# Gateway_v1_0.net
KiCad netlist of a schematic drawn in EAGLE
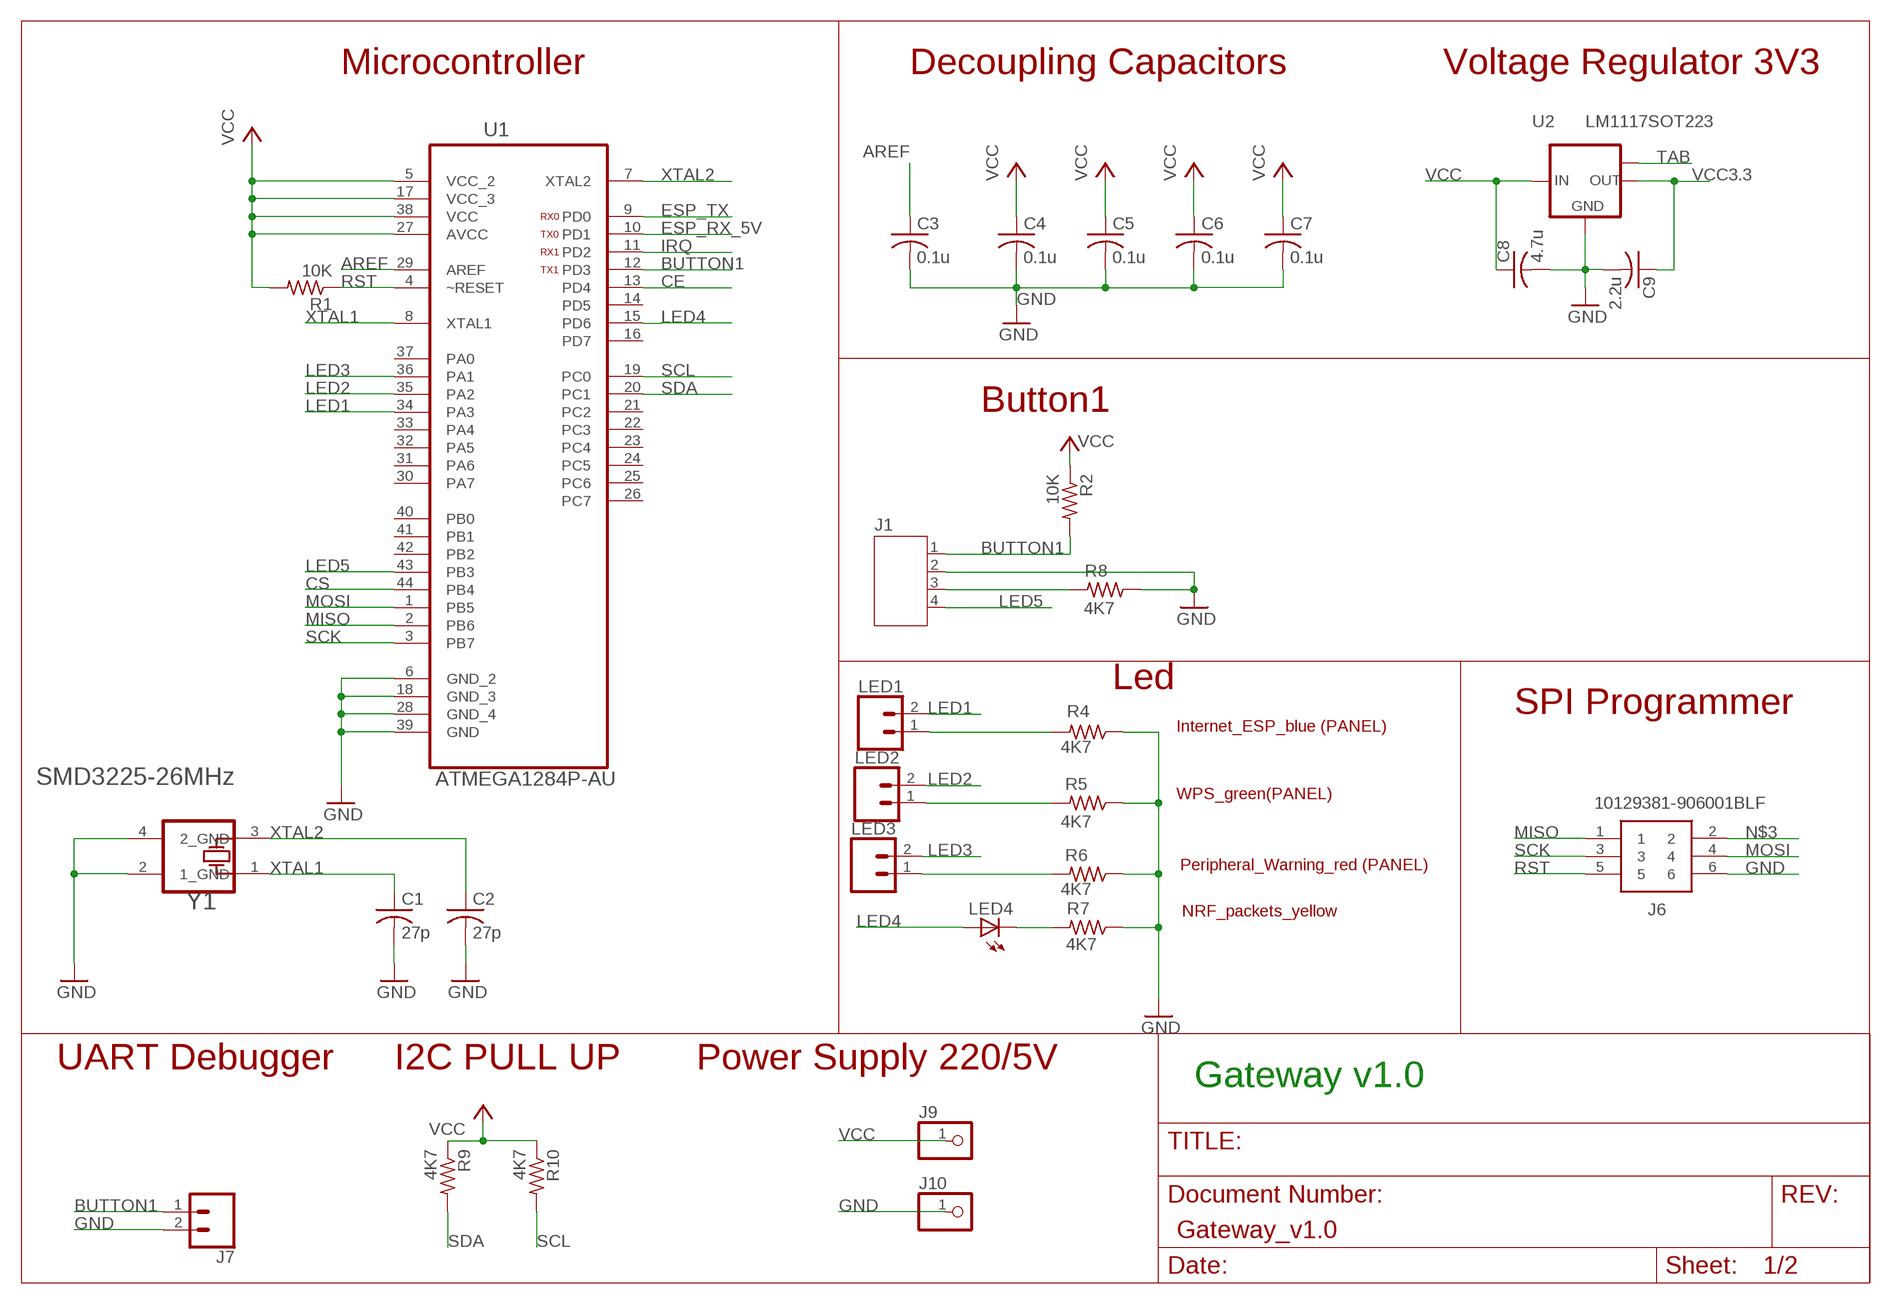
[diagram p0: schematic, sheet 1]
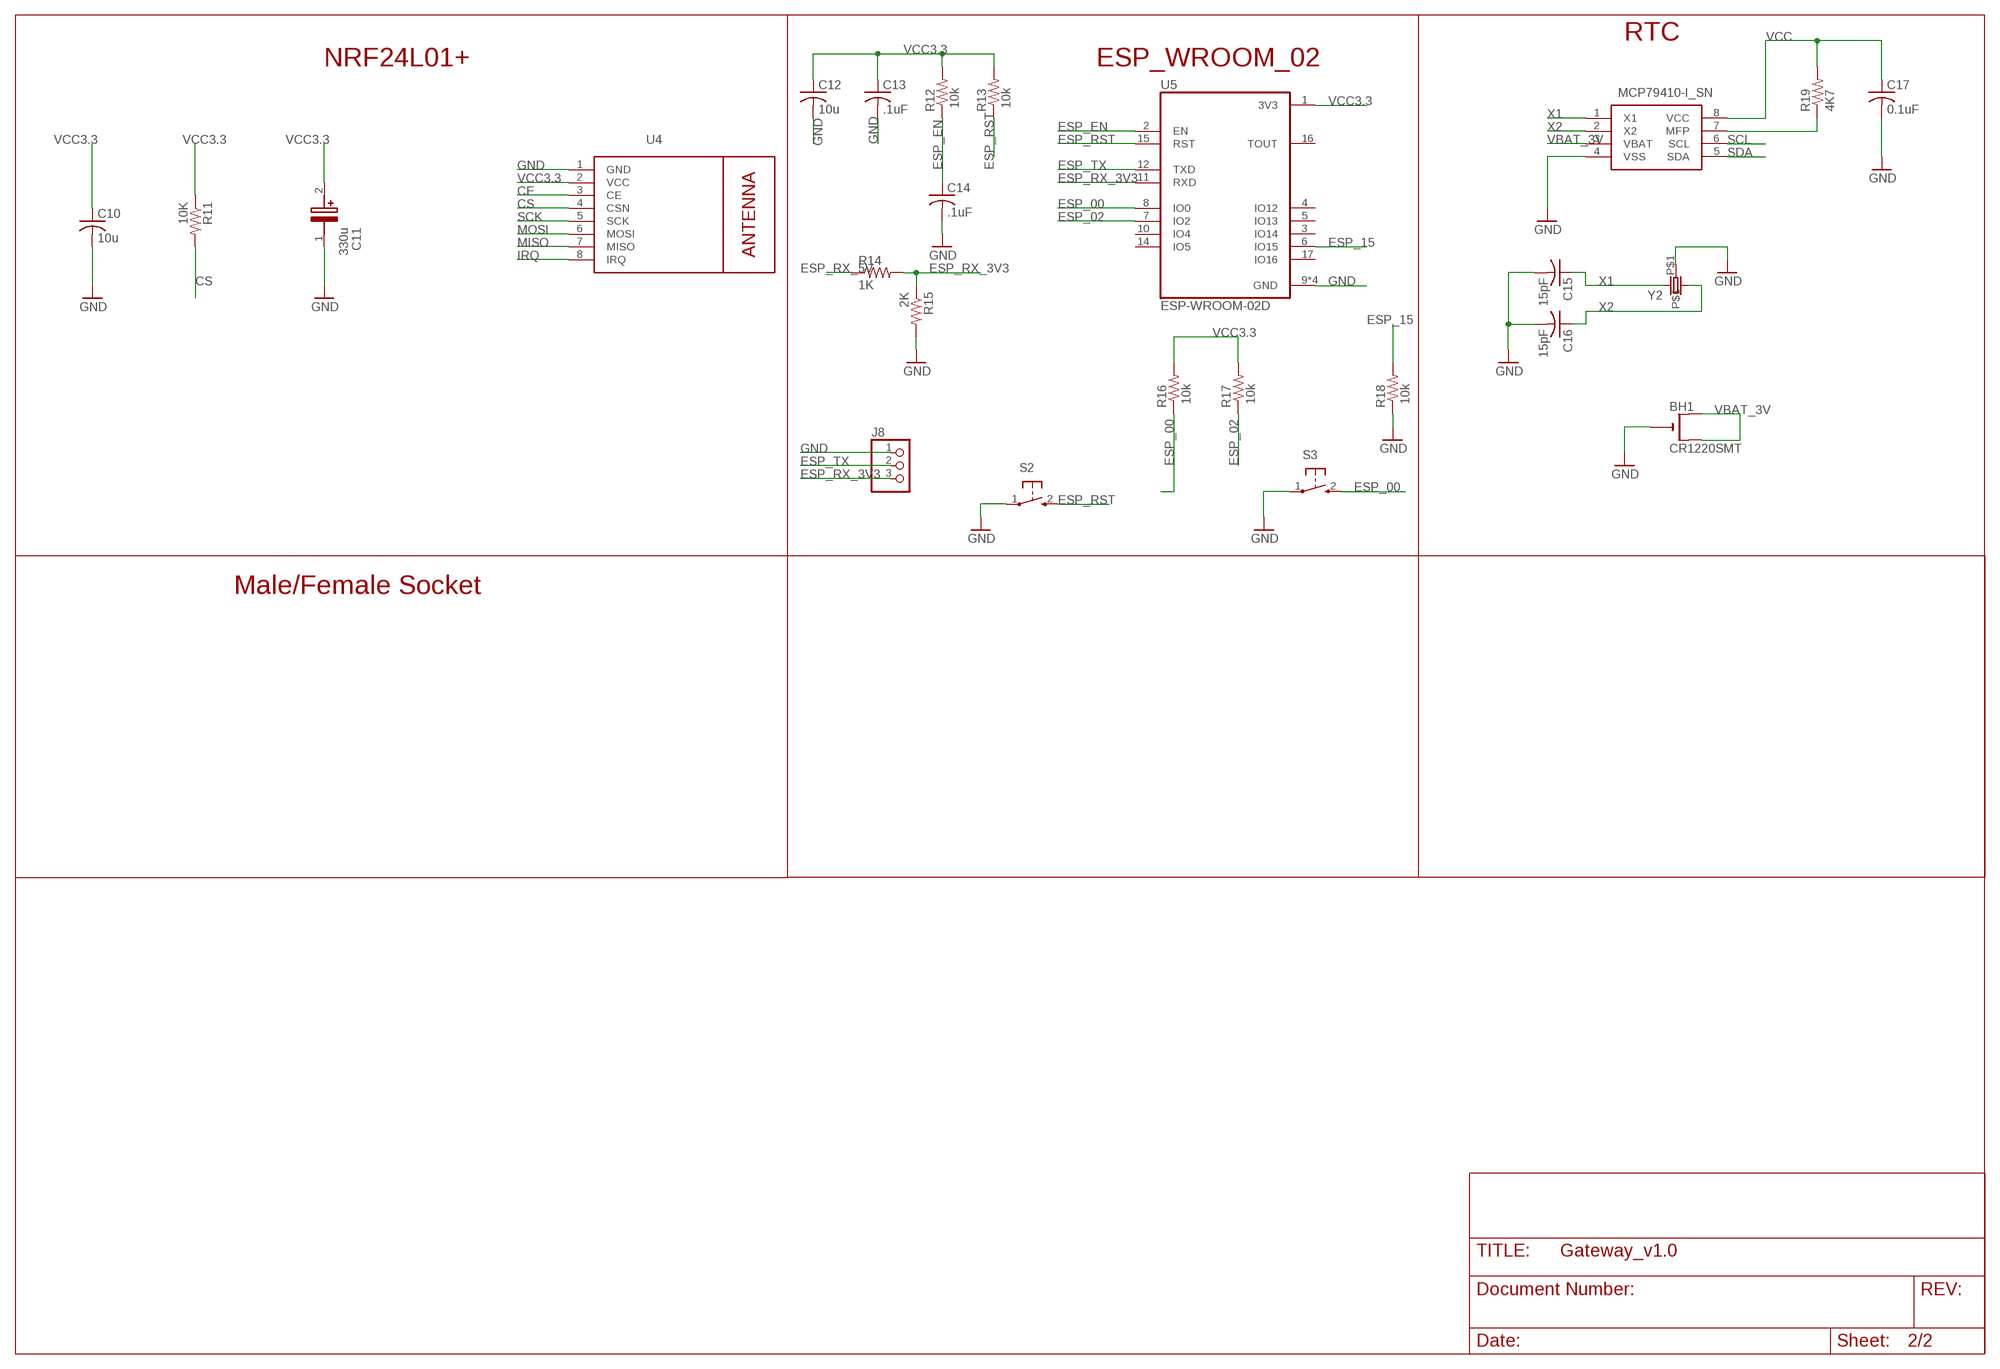
[diagram p1: schematic, sheet 2]

(export (version "E")
  (design (tool "Eeschema 10.0.6"))
  (components
    (comp (ref "C1")
      (value "27p")
      (footprint "eagle-import:SMD-0805")
      (libsource (lib "eagle-import") (part "CAPACITOR-SMD-0805"))
    )
    (comp (ref "C2")
      (value "27p")
      (footprint "eagle-import:SMD-0805")
      (libsource (lib "eagle-import") (part "CAPACITOR-SMD-0805"))
    )
    (comp (ref "C3")
      (value "0.1u")
      (footprint "eagle-import:SMD-0805")
      (libsource (lib "eagle-import") (part "CAPACITOR-SMD-0805"))
    )
    (comp (ref "C4")
      (value "0.1u")
      (footprint "eagle-import:SMD-0805")
      (libsource (lib "eagle-import") (part "CAPACITOR-SMD-0805"))
    )
    (comp (ref "C5")
      (value "0.1u")
      (footprint "eagle-import:SMD-0805")
      (libsource (lib "eagle-import") (part "CAPACITOR-SMD-0805"))
    )
    (comp (ref "C6")
      (value "0.1u")
      (footprint "eagle-import:SMD-0805")
      (libsource (lib "eagle-import") (part "CAPACITOR-SMD-0805"))
    )
    (comp (ref "C7")
      (value "0.1u")
      (footprint "eagle-import:SMD-0805")
      (libsource (lib "eagle-import") (part "CAPACITOR-SMD-0805"))
    )
    (comp (ref "C8")
      (value "4.7u")
      (footprint "eagle-import:SMD-0805")
      (libsource (lib "eagle-import") (part "CAPACITOR-SMD-0805"))
    )
    (comp (ref "C9")
      (value "2.2u")
      (footprint "eagle-import:SMD-0805")
      (libsource (lib "eagle-import") (part "CAPACITOR-SMD-0805"))
    )
    (comp (ref "J1")
      (value "JST-PH4")
      (footprint "eagle-import:JST-PH4")
      (libsource (lib "eagle-import") (part "JST-PH4"))
    )
    (comp (ref "J6")
      (value "10129381-906001BLF")
      (footprint "eagle-import:HDRV6W67P254_2X3_762X483X858P")
      (fields (field (name "MOUSER_PART_NUMBER") "649-1012938190601BLF"))
      (libsource (lib "eagle-import") (part "10129381-906001BLF"))
    )
    (comp (ref "J7")
      (value "CONN_02")
      (footprint "eagle-import:1X02")
      (libsource (lib "eagle-import") (part "CONN_02"))
    )
    (comp (ref "J9")
      (value "PINHD-1X1CB")
      (footprint "eagle-import:1X01-CLEANBIG")
      (libsource (lib "eagle-import") (part "PINHD-1X1CB"))
    )
    (comp (ref "J10")
      (value "PINHD-1X1CB")
      (footprint "eagle-import:1X01-CLEANBIG")
      (libsource (lib "eagle-import") (part "PINHD-1X1CB"))
    )
    (comp (ref "LED1")
      (value "CONN_02")
      (footprint "eagle-import:1X02")
      (libsource (lib "eagle-import") (part "CONN_02"))
    )
    (comp (ref "LED2")
      (value "CONN_02")
      (footprint "eagle-import:1X02")
      (libsource (lib "eagle-import") (part "CONN_02"))
    )
    (comp (ref "LED3")
      (value "CONN_02")
      (footprint "eagle-import:1X02")
      (libsource (lib "eagle-import") (part "CONN_02"))
    )
    (comp (ref "LED4")
      (value "LED4")
      (footprint "eagle-import:SMD-0805-LED")
      (libsource (lib "eagle-import") (part "LED-SMD-0805"))
    )
    (comp (ref "R1")
      (value "10K")
      (footprint "eagle-import:SMD-0805")
      (libsource (lib "eagle-import") (part "RESISTOR-SMD-0805"))
    )
    (comp (ref "R2")
      (value "10K")
      (footprint "eagle-import:SMD-0805")
      (libsource (lib "eagle-import") (part "RESISTOR-SMD-0805"))
    )
    (comp (ref "R4")
      (value "4K7")
      (footprint "eagle-import:SMD-0805")
      (libsource (lib "eagle-import") (part "RESISTOR-SMD-0805"))
    )
    (comp (ref "R5")
      (value "4K7")
      (footprint "eagle-import:SMD-0805")
      (libsource (lib "eagle-import") (part "RESISTOR-SMD-0805"))
    )
    (comp (ref "R6")
      (value "4K7")
      (footprint "eagle-import:SMD-0805")
      (libsource (lib "eagle-import") (part "RESISTOR-SMD-0805"))
    )
    (comp (ref "R7")
      (value "4K7")
      (footprint "eagle-import:SMD-0805")
      (libsource (lib "eagle-import") (part "RESISTOR-SMD-0805"))
    )
    (comp (ref "R8")
      (value "4K7")
      (footprint "eagle-import:SMD-0805")
      (libsource (lib "eagle-import") (part "RESISTOR-SMD-0805"))
    )
    (comp (ref "R9")
      (value "4K7")
      (footprint "eagle-import:SMD-0805")
      (libsource (lib "eagle-import") (part "RESISTOR-SMD-0805"))
    )
    (comp (ref "R10")
      (value "4K7")
      (footprint "eagle-import:SMD-0805")
      (libsource (lib "eagle-import") (part "RESISTOR-SMD-0805"))
    )
    (comp (ref "U1")
      (value "ATMEGA1284P-AU")
      (footprint "eagle-import:QFP80P1200X1200X120-44N")
      (fields (field (name "MF") "Microchip"))
      (libsource (lib "eagle-import") (part "ATMEGA1284P-AU"))
    )
    (comp (ref "U2")
      (value "LM1117SOT223")
      (footprint "eagle-import:SOT223")
      (libsource (lib "eagle-import") (part "LM1117MPX-3.3"))
    )
    (comp (ref "Y1")
      (value "TND_ELECTRONIC_SMD3225-26MHZTND_ELECTRONIC_SMD3225-26MHZ_0_0")
      (footprint "eagle-import:TND_ELECTRONIC_SMD3225-26MHZ_0")
      (fields (field (name "MF") "TND Electronic") (field (name "MPN") "SMD3225-26MHz"))
      (libsource (lib "eagle-import") (part "TND_ELECTRONIC_SMD3225-26MHZTND_ELECTRONIC_SMD3225-26MHZ_0_0"))
    )
    (comp (ref "BH1")
      (value "CR1220SMT")
      (footprint "eagle-import:CR1220-SMD")
      (fields (field (name "MF") "FDK America,") (field (name "MP") "CR1220"))
      (libsource (lib "eagle-import") (part "CR1220SMT"))
    )
    (comp (ref "C10")
      (value "10u")
      (footprint "eagle-import:SMD-0805")
      (libsource (lib "eagle-import") (part "CAPACITOR-SMD-0805"))
    )
    (comp (ref "C11")
      (value "330u")
      (footprint "eagle-import:SMD_LYTIC_D8")
      (fields
        (field (name "MANUFACTURER_PART_NUMBER") "EEE-FNC271XUP")
        (field (name "MOUSER_PART_NUMBER") "667-EEE-FNC271XUP")
      )
      (libsource (lib "eagle-import") (part "EEE-FNC271XUP"))
    )
    (comp (ref "C12")
      (value "10u")
      (footprint "eagle-import:SMD-0805")
      (libsource (lib "eagle-import") (part "CAPACITOR-SMD-0805"))
    )
    (comp (ref "C13")
      (value ".1uF")
      (footprint "eagle-import:SMD-0805")
      (libsource (lib "eagle-import") (part "CAPACITOR-SMD-0805"))
    )
    (comp (ref "C14")
      (value ".1uF")
      (footprint "eagle-import:SMD-0805")
      (libsource (lib "eagle-import") (part "CAPACITOR-SMD-0805"))
    )
    (comp (ref "C15")
      (value "15pF")
      (footprint "eagle-import:SMD-0805")
      (libsource (lib "eagle-import") (part "CAPACITOR-SMD-0805"))
    )
    (comp (ref "C16")
      (value "15pF")
      (footprint "eagle-import:SMD-0805")
      (libsource (lib "eagle-import") (part "CAPACITOR-SMD-0805"))
    )
    (comp (ref "C17")
      (value "0.1uF")
      (footprint "eagle-import:SMD-0805")
      (libsource (lib "eagle-import") (part "CAPACITOR-SMD-0805"))
    )
    (comp (ref "J8")
      (value "PINHD-1X3")
      (footprint "eagle-import:1X03")
      (libsource (lib "eagle-import") (part "PINHD-1X3"))
    )
    (comp (ref "R11")
      (value "10K")
      (footprint "eagle-import:SMD-0805")
      (libsource (lib "eagle-import") (part "RESISTOR-SMD-0805"))
    )
    (comp (ref "R12")
      (value "10k")
      (footprint "eagle-import:SMD-0805")
      (libsource (lib "eagle-import") (part "RESISTOR-SMD-0805"))
    )
    (comp (ref "R13")
      (value "10k")
      (footprint "eagle-import:SMD-0805")
      (libsource (lib "eagle-import") (part "RESISTOR-SMD-0805"))
    )
    (comp (ref "R14")
      (value "1K")
      (footprint "eagle-import:SMD-0805")
      (libsource (lib "eagle-import") (part "RESISTOR-SMD-0805"))
    )
    (comp (ref "R15")
      (value "2K")
      (footprint "eagle-import:SMD-0805")
      (libsource (lib "eagle-import") (part "RESISTOR-SMD-0805"))
    )
    (comp (ref "R16")
      (value "10k")
      (footprint "eagle-import:SMD-0805")
      (libsource (lib "eagle-import") (part "RESISTOR-SMD-0805"))
    )
    (comp (ref "R17")
      (value "10k")
      (footprint "eagle-import:SMD-0805")
      (libsource (lib "eagle-import") (part "RESISTOR-SMD-0805"))
    )
    (comp (ref "R18")
      (value "10k")
      (footprint "eagle-import:SMD-0805")
      (libsource (lib "eagle-import") (part "RESISTOR-SMD-0805"))
    )
    (comp (ref "R19")
      (value "4K7")
      (footprint "eagle-import:SMD-0805")
      (libsource (lib "eagle-import") (part "RESISTOR-SMD-0805"))
    )
    (comp (ref "S2")
      (value "SPST_TACT-KMR2")
      (footprint "eagle-import:KMR2")
      (libsource (lib "eagle-import") (part "SPST_TACT-KMR2"))
    )
    (comp (ref "S3")
      (value "SPST_TACT-KMR2")
      (footprint "eagle-import:KMR2")
      (libsource (lib "eagle-import") (part "SPST_TACT-KMR2"))
    )
    (comp (ref "U4")
      (value "WIRELESS-NRF24L01")
      (footprint "eagle-import:WIRELESS-NRF24L01")
      (libsource (lib "eagle-import") (part "WIRELESS-NRF24L01"))
    )
    (comp (ref "U5")
      (value "ESP-WROOM-02D")
      (footprint "eagle-import:MODULE_ESP-WROOM-02D")
      (fields (field (name "MF") "Espressif Systems"))
      (libsource (lib "eagle-import") (part "ESP-WROOM-02D"))
    )
    (comp (ref "U6")
      (value "MCP79410-I_SN")
      (footprint "eagle-import:SOIC127P600X175-8N")
      (fields
        (field (name "MANUFACTURER_PART_NUMBER") "MCP79410-I/SN")
        (field (name "MOUSER_PART_NUMBER") "579-MCP79410-I/SN")
      )
      (libsource (lib "eagle-import") (part "MCP79410-I_SN"))
    )
    (comp (ref "Y2")
      (value "CRYSTALTC26H")
      (footprint "eagle-import:TC26H")
      (libsource (lib "eagle-import") (part "CRYSTALTC26H"))
    )
  )
  (nets
    (net (code "1") (name "AREF") (class "Default")
      (node (ref "C3") (pin "1") (pinfunction "1_1") (pintype "passive"))
      (node (ref "U1") (pin "29") (pinfunction "AREF_29") (pintype "input"))
    )
    (net (code "2") (name "BUTTON1") (class "Default")
      (node (ref "J1") (pin "1") (pinfunction "1_1") (pintype "passive"))
      (node (ref "J7") (pin "1") (pinfunction "1_1") (pintype "passive"))
      (node (ref "R2") (pin "2") (pinfunction "2_2") (pintype "passive"))
      (node (ref "U1") (pin "12") (pinfunction "PD3_12") (pintype "bidirectional"))
    )
    (net (code "3") (name "CE") (class "Default")
      (node (ref "U1") (pin "13") (pinfunction "PD4_13") (pintype "bidirectional"))
      (node (ref "U4") (pin "3") (pinfunction "CE_3") (pintype "bidirectional"))
    )
    (net (code "4") (name "CS") (class "Default")
      (node (ref "R11") (pin "2") (pinfunction "2_2") (pintype "passive"))
      (node (ref "U1") (pin "44") (pinfunction "PB4_44") (pintype "bidirectional"))
      (node (ref "U4") (pin "4") (pinfunction "CSN_4") (pintype "bidirectional"))
    )
    (net (code "5") (name "ESP_00") (class "Default")
      (node (ref "R16") (pin "1") (pinfunction "1_1") (pintype "passive"))
      (node (ref "S3") (pin "2") (pinfunction "S_2") (pintype "passive"))
      (node (ref "U5") (pin "8") (pinfunction "IO0_8") (pintype "bidirectional"))
    )
    (net (code "6") (name "ESP_02") (class "Default")
      (node (ref "R17") (pin "1") (pinfunction "1_1") (pintype "passive"))
      (node (ref "U5") (pin "7") (pinfunction "IO2_7") (pintype "bidirectional"))
    )
    (net (code "7") (name "ESP_15") (class "Default")
      (node (ref "R18") (pin "2") (pinfunction "2_2") (pintype "passive"))
      (node (ref "U5") (pin "6") (pinfunction "IO15_6") (pintype "bidirectional"))
    )
    (net (code "8") (name "ESP_EN") (class "Default")
      (node (ref "C14") (pin "1") (pinfunction "1_1") (pintype "passive"))
      (node (ref "R12") (pin "1") (pinfunction "1_1") (pintype "passive"))
      (node (ref "U5") (pin "2") (pinfunction "EN_2") (pintype "input"))
    )
    (net (code "9") (name "ESP_RST") (class "Default")
      (node (ref "R13") (pin "1") (pinfunction "1_1") (pintype "passive"))
      (node (ref "S2") (pin "2") (pinfunction "S_2") (pintype "passive"))
      (node (ref "U5") (pin "15") (pinfunction "RST_15") (pintype "input"))
    )
    (net (code "10") (name "ESP_RX_3V3") (class "Default")
      (node (ref "J8") (pin "3") (pinfunction "3_3") (pintype "passive"))
      (node (ref "R14") (pin "2") (pinfunction "2_2") (pintype "passive"))
      (node (ref "R15") (pin "1") (pinfunction "1_1") (pintype "passive"))
      (node (ref "U5") (pin "11") (pinfunction "RXD_11") (pintype "bidirectional"))
    )
    (net (code "11") (name "ESP_RX_5V") (class "Default")
      (node (ref "R14") (pin "1") (pinfunction "1_1") (pintype "passive"))
      (node (ref "U1") (pin "10") (pinfunction "PD1_10") (pintype "bidirectional"))
    )
    (net (code "12") (name "ESP_TX") (class "Default")
      (node (ref "J8") (pin "2") (pinfunction "2_2") (pintype "passive"))
      (node (ref "U1") (pin "9") (pinfunction "PD0_9") (pintype "bidirectional"))
      (node (ref "U5") (pin "12") (pinfunction "TXD_12") (pintype "bidirectional"))
    )
    (net (code "13") (name "GND") (class "Default")
      (node (ref "BH1") (pin "-") (pinfunction "-_-") (pintype "passive"))
      (node (ref "C1") (pin "2") (pinfunction "2_2") (pintype "passive"))
      (node (ref "C10") (pin "2") (pinfunction "2_2") (pintype "passive"))
      (node (ref "C11") (pin "1") (pinfunction "1_1") (pintype "bidirectional"))
      (node (ref "C12") (pin "2") (pinfunction "2_2") (pintype "passive"))
      (node (ref "C13") (pin "2") (pinfunction "2_2") (pintype "passive"))
      (node (ref "C14") (pin "2") (pinfunction "2_2") (pintype "passive"))
      (node (ref "C15") (pin "2") (pinfunction "2_2") (pintype "passive"))
      (node (ref "C16") (pin "2") (pinfunction "2_2") (pintype "passive"))
      (node (ref "C17") (pin "2") (pinfunction "2_2") (pintype "passive"))
      (node (ref "C2") (pin "2") (pinfunction "2_2") (pintype "passive"))
      (node (ref "C3") (pin "2") (pinfunction "2_2") (pintype "passive"))
      (node (ref "C4") (pin "2") (pinfunction "2_2") (pintype "passive"))
      (node (ref "C5") (pin "2") (pinfunction "2_2") (pintype "passive"))
      (node (ref "C6") (pin "2") (pinfunction "2_2") (pintype "passive"))
      (node (ref "C7") (pin "2") (pinfunction "2_2") (pintype "passive"))
      (node (ref "C8") (pin "2") (pinfunction "2_2") (pintype "passive"))
      (node (ref "C9") (pin "2") (pinfunction "2_2") (pintype "passive"))
      (node (ref "J1") (pin "2") (pinfunction "2_2") (pintype "passive"))
      (node (ref "J10") (pin "1") (pinfunction "1_1") (pintype "passive"))
      (node (ref "J6") (pin "6") (pinfunction "6_6") (pintype "bidirectional"))
      (node (ref "J7") (pin "2") (pinfunction "2_2") (pintype "passive"))
      (node (ref "J8") (pin "1") (pinfunction "1_1") (pintype "passive"))
      (node (ref "R15") (pin "2") (pinfunction "2_2") (pintype "passive"))
      (node (ref "R18") (pin "1") (pinfunction "1_1") (pintype "passive"))
      (node (ref "R4") (pin "1") (pinfunction "1_1") (pintype "passive"))
      (node (ref "R5") (pin "1") (pinfunction "1_1") (pintype "passive"))
      (node (ref "R6") (pin "1") (pinfunction "1_1") (pintype "passive"))
      (node (ref "R7") (pin "1") (pinfunction "1_1") (pintype "passive"))
      (node (ref "R8") (pin "1") (pinfunction "1_1") (pintype "passive"))
      (node (ref "S2") (pin "1") (pinfunction "P_1") (pintype "passive"))
      (node (ref "S3") (pin "1") (pinfunction "P_1") (pintype "passive"))
      (node (ref "U1") (pin "18") (pinfunction "GND_3_18") (pintype "passive"))
      (node (ref "U1") (pin "28") (pinfunction "GND_4_28") (pintype "passive"))
      (node (ref "U1") (pin "39") (pinfunction "GND_39") (pintype "passive"))
      (node (ref "U1") (pin "6") (pinfunction "GND_2_6") (pintype "passive"))
      (node (ref "U2") (pin "1") (pinfunction "GND_1") (pintype "input"))
      (node (ref "U4") (pin "1") (pinfunction "GND_1") (pintype "power_in"))
      (node (ref "U5") (pin "13") (pinfunction "GND_13") (pintype "power_in"))
      (node (ref "U5") (pin "18") (pinfunction "GND_18") (pintype "power_in"))
      (node (ref "U5") (pin "19") (pinfunction "GND_19") (pintype "power_in"))
      (node (ref "U5") (pin "9") (pinfunction "GND_9") (pintype "power_in"))
      (node (ref "U6") (pin "4") (pinfunction "VSS_4") (pintype "power_in"))
      (node (ref "Y1") (pin "2") (pinfunction "1_GND_2") (pintype "power_in"))
      (node (ref "Y1") (pin "4") (pinfunction "2_GND_4") (pintype "power_in"))
      (node (ref "Y2") (pin "P$1") (pinfunction "P$1_P$1") (pintype "passive"))
    )
    (net (code "14") (name "IRQ") (class "Default")
      (node (ref "U1") (pin "11") (pinfunction "PD2_11") (pintype "bidirectional"))
      (node (ref "U4") (pin "8") (pinfunction "IRQ_8") (pintype "bidirectional"))
    )
    (net (code "15") (name "LED1") (class "Default")
      (node (ref "LED1") (pin "2") (pinfunction "2_2") (pintype "passive"))
      (node (ref "U1") (pin "34") (pinfunction "PA3_34") (pintype "bidirectional"))
    )
    (net (code "16") (name "LED2") (class "Default")
      (node (ref "LED2") (pin "2") (pinfunction "2_2") (pintype "passive"))
      (node (ref "U1") (pin "35") (pinfunction "PA2_35") (pintype "bidirectional"))
    )
    (net (code "17") (name "LED3") (class "Default")
      (node (ref "LED3") (pin "2") (pinfunction "2_2") (pintype "passive"))
      (node (ref "U1") (pin "36") (pinfunction "PA1_36") (pintype "bidirectional"))
    )
    (net (code "18") (name "LED4") (class "Default")
      (node (ref "LED4") (pin "1") (pinfunction "A_1") (pintype "passive"))
      (node (ref "U1") (pin "15") (pinfunction "PD6_15") (pintype "bidirectional"))
    )
    (net (code "19") (name "LED5") (class "Default")
      (node (ref "J1") (pin "4") (pinfunction "4_4") (pintype "passive"))
      (node (ref "U1") (pin "43") (pinfunction "PB3_43") (pintype "bidirectional"))
    )
    (net (code "20") (name "MISO") (class "Default")
      (node (ref "J6") (pin "1") (pinfunction "1_1") (pintype "bidirectional"))
      (node (ref "U1") (pin "2") (pinfunction "PB6_2") (pintype "bidirectional"))
      (node (ref "U4") (pin "7") (pinfunction "MISO_7") (pintype "bidirectional"))
    )
    (net (code "21") (name "MOSI") (class "Default")
      (node (ref "J6") (pin "4") (pinfunction "4_4") (pintype "bidirectional"))
      (node (ref "U1") (pin "1") (pinfunction "PB5_1") (pintype "bidirectional"))
      (node (ref "U4") (pin "6") (pinfunction "MOSI_6") (pintype "bidirectional"))
    )
    (net (code "22") (name "N$3") (class "Default")
      (node (ref "J6") (pin "2") (pinfunction "2_2") (pintype "bidirectional"))
    )
    (net (code "23") (name "Net-(J1-Pad3)") (class "Default")
      (node (ref "J1") (pin "3") (pinfunction "3_3") (pintype "passive"))
      (node (ref "R8") (pin "2") (pinfunction "2_2") (pintype "passive"))
    )
    (net (code "24") (name "Net-(LED1-Pad1)") (class "Default")
      (node (ref "LED1") (pin "1") (pinfunction "1_1") (pintype "passive"))
      (node (ref "R4") (pin "2") (pinfunction "2_2") (pintype "passive"))
    )
    (net (code "25") (name "Net-(LED2-Pad1)") (class "Default")
      (node (ref "LED2") (pin "1") (pinfunction "1_1") (pintype "passive"))
      (node (ref "R5") (pin "2") (pinfunction "2_2") (pintype "passive"))
    )
    (net (code "26") (name "Net-(LED3-Pad1)") (class "Default")
      (node (ref "LED3") (pin "1") (pinfunction "1_1") (pintype "passive"))
      (node (ref "R6") (pin "2") (pinfunction "2_2") (pintype "passive"))
    )
    (net (code "27") (name "Net-(LED4-C)") (class "Default")
      (node (ref "LED4") (pin "2") (pinfunction "C_2") (pintype "passive"))
      (node (ref "R7") (pin "2") (pinfunction "2_2") (pintype "passive"))
    )
    (net (code "28") (name "Net-(U6-MFP)") (class "Default")
      (node (ref "R19") (pin "1") (pinfunction "1_1") (pintype "passive"))
      (node (ref "U6") (pin "7") (pinfunction "MFP_7") (pintype "bidirectional"))
    )
    (net (code "29") (name "RST") (class "Default")
      (node (ref "J6") (pin "5") (pinfunction "5_5") (pintype "bidirectional"))
      (node (ref "R1") (pin "1") (pinfunction "1_1") (pintype "passive"))
      (node (ref "U1") (pin "4") (pinfunction "~{RESET}_4") (pintype "input"))
    )
    (net (code "30") (name "SCK") (class "Default")
      (node (ref "J6") (pin "3") (pinfunction "3_3") (pintype "bidirectional"))
      (node (ref "U1") (pin "3") (pinfunction "PB7_3") (pintype "bidirectional"))
      (node (ref "U4") (pin "5") (pinfunction "SCK_5") (pintype "bidirectional"))
    )
    (net (code "31") (name "SCL") (class "Default")
      (node (ref "R10") (pin "2") (pinfunction "2_2") (pintype "passive"))
      (node (ref "U1") (pin "19") (pinfunction "PC0_19") (pintype "bidirectional"))
      (node (ref "U6") (pin "6") (pinfunction "SCL_6") (pintype "bidirectional"))
    )
    (net (code "32") (name "SDA") (class "Default")
      (node (ref "R9") (pin "2") (pinfunction "2_2") (pintype "passive"))
      (node (ref "U1") (pin "20") (pinfunction "PC1_20") (pintype "bidirectional"))
      (node (ref "U6") (pin "5") (pinfunction "SDA_5") (pintype "bidirectional"))
    )
    (net (code "33") (name "VBAT_3V") (class "Default")
      (node (ref "BH1") (pin "+$1") (pinfunction "+_+$1") (pintype "passive"))
      (node (ref "BH1") (pin "+$2") (pinfunction "+1_+$2") (pintype "passive"))
      (node (ref "U6") (pin "3") (pinfunction "VBAT_3") (pintype "bidirectional"))
    )
    (net (code "34") (name "VCC") (class "Default")
      (node (ref "C17") (pin "1") (pinfunction "1_1") (pintype "passive"))
      (node (ref "C4") (pin "1") (pinfunction "1_1") (pintype "passive"))
      (node (ref "C5") (pin "1") (pinfunction "1_1") (pintype "passive"))
      (node (ref "C6") (pin "1") (pinfunction "1_1") (pintype "passive"))
      (node (ref "C7") (pin "1") (pinfunction "1_1") (pintype "passive"))
      (node (ref "C8") (pin "1") (pinfunction "1_1") (pintype "passive"))
      (node (ref "J9") (pin "1") (pinfunction "1_1") (pintype "passive"))
      (node (ref "R1") (pin "2") (pinfunction "2_2") (pintype "passive"))
      (node (ref "R10") (pin "1") (pinfunction "1_1") (pintype "passive"))
      (node (ref "R19") (pin "2") (pinfunction "2_2") (pintype "passive"))
      (node (ref "R2") (pin "1") (pinfunction "1_1") (pintype "passive"))
      (node (ref "R9") (pin "1") (pinfunction "1_1") (pintype "passive"))
      (node (ref "U1") (pin "17") (pinfunction "VCC_3_17") (pintype "power_in"))
      (node (ref "U1") (pin "27") (pinfunction "AVCC_27") (pintype "power_in"))
      (node (ref "U1") (pin "38") (pinfunction "VCC_38") (pintype "power_in"))
      (node (ref "U1") (pin "5") (pinfunction "VCC_2_5") (pintype "power_in"))
      (node (ref "U2") (pin "3") (pinfunction "IN_3") (pintype "input"))
      (node (ref "U6") (pin "8") (pinfunction "VCC_8") (pintype "power_in"))
    )
    (net (code "35") (name "VCC3.3") (class "Default")
      (node (ref "C10") (pin "1") (pinfunction "1_1") (pintype "passive"))
      (node (ref "C11") (pin "2") (pinfunction "2_2") (pintype "bidirectional"))
      (node (ref "C12") (pin "1") (pinfunction "1_1") (pintype "passive"))
      (node (ref "C13") (pin "1") (pinfunction "1_1") (pintype "passive"))
      (node (ref "C9") (pin "1") (pinfunction "1_1") (pintype "passive"))
      (node (ref "R11") (pin "1") (pinfunction "1_1") (pintype "passive"))
      (node (ref "R12") (pin "2") (pinfunction "2_2") (pintype "passive"))
      (node (ref "R13") (pin "2") (pinfunction "2_2") (pintype "passive"))
      (node (ref "R16") (pin "2") (pinfunction "2_2") (pintype "passive"))
      (node (ref "R17") (pin "2") (pinfunction "2_2") (pintype "passive"))
      (node (ref "U2") (pin "2") (pinfunction "OUT_2") (pintype "passive"))
      (node (ref "U4") (pin "2") (pinfunction "VCC_2") (pintype "power_in"))
      (node (ref "U5") (pin "1") (pinfunction "3V3_1") (pintype "power_in"))
    )
    (net (code "36") (name "X1") (class "Default")
      (node (ref "C15") (pin "1") (pinfunction "1_1") (pintype "passive"))
      (node (ref "U6") (pin "1") (pinfunction "X1_1") (pintype "bidirectional"))
      (node (ref "Y2") (pin "2") (pinfunction "2_2") (pintype "passive"))
    )
    (net (code "37") (name "X2") (class "Default")
      (node (ref "C16") (pin "1") (pinfunction "1_1") (pintype "passive"))
      (node (ref "U6") (pin "2") (pinfunction "X2_2") (pintype "bidirectional"))
      (node (ref "Y2") (pin "1") (pinfunction "1_1") (pintype "passive"))
    )
    (net (code "38") (name "XTAL1") (class "Default")
      (node (ref "C1") (pin "1") (pinfunction "1_1") (pintype "passive"))
      (node (ref "U1") (pin "8") (pinfunction "XTAL1_8") (pintype "input"))
      (node (ref "Y1") (pin "1") (pinfunction "X1_1") (pintype "passive"))
    )
    (net (code "39") (name "XTAL2") (class "Default")
      (node (ref "C2") (pin "1") (pinfunction "1_1") (pintype "passive"))
      (node (ref "U1") (pin "7") (pinfunction "XTAL2_7") (pintype "output"))
      (node (ref "Y1") (pin "3") (pinfunction "X2_3") (pintype "passive"))
    )
    (net (code "40") (name "unconnected-(U1-PA0-Pad37)") (class "Default")
      (node (ref "U1") (pin "37") (pinfunction "PA0_37") (pintype "bidirectional"))
    )
    (net (code "41") (name "unconnected-(U1-PA4-Pad33)") (class "Default")
      (node (ref "U1") (pin "33") (pinfunction "PA4_33") (pintype "bidirectional"))
    )
    (net (code "42") (name "unconnected-(U1-PA5-Pad32)") (class "Default")
      (node (ref "U1") (pin "32") (pinfunction "PA5_32") (pintype "bidirectional"))
    )
    (net (code "43") (name "unconnected-(U1-PA6-Pad31)") (class "Default")
      (node (ref "U1") (pin "31") (pinfunction "PA6_31") (pintype "bidirectional"))
    )
    (net (code "44") (name "unconnected-(U1-PA7-Pad30)") (class "Default")
      (node (ref "U1") (pin "30") (pinfunction "PA7_30") (pintype "bidirectional"))
    )
    (net (code "45") (name "unconnected-(U1-PB0-Pad40)") (class "Default")
      (node (ref "U1") (pin "40") (pinfunction "PB0_40") (pintype "bidirectional"))
    )
    (net (code "46") (name "unconnected-(U1-PB1-Pad41)") (class "Default")
      (node (ref "U1") (pin "41") (pinfunction "PB1_41") (pintype "bidirectional"))
    )
    (net (code "47") (name "unconnected-(U1-PB2-Pad42)") (class "Default")
      (node (ref "U1") (pin "42") (pinfunction "PB2_42") (pintype "bidirectional"))
    )
    (net (code "48") (name "unconnected-(U1-PC2-Pad21)") (class "Default")
      (node (ref "U1") (pin "21") (pinfunction "PC2_21") (pintype "bidirectional"))
    )
    (net (code "49") (name "unconnected-(U1-PC3-Pad22)") (class "Default")
      (node (ref "U1") (pin "22") (pinfunction "PC3_22") (pintype "bidirectional"))
    )
    (net (code "50") (name "unconnected-(U1-PC4-Pad23)") (class "Default")
      (node (ref "U1") (pin "23") (pinfunction "PC4_23") (pintype "bidirectional"))
    )
    (net (code "51") (name "unconnected-(U1-PC5-Pad24)") (class "Default")
      (node (ref "U1") (pin "24") (pinfunction "PC5_24") (pintype "bidirectional"))
    )
    (net (code "52") (name "unconnected-(U1-PC6-Pad25)") (class "Default")
      (node (ref "U1") (pin "25") (pinfunction "PC6_25") (pintype "bidirectional"))
    )
    (net (code "53") (name "unconnected-(U1-PC7-Pad26)") (class "Default")
      (node (ref "U1") (pin "26") (pinfunction "PC7_26") (pintype "bidirectional"))
    )
    (net (code "54") (name "unconnected-(U1-PD5-Pad14)") (class "Default")
      (node (ref "U1") (pin "14") (pinfunction "PD5_14") (pintype "bidirectional"))
    )
    (net (code "55") (name "unconnected-(U1-PD7-Pad16)") (class "Default")
      (node (ref "U1") (pin "16") (pinfunction "PD7_16") (pintype "bidirectional"))
    )
    (net (code "56") (name "unconnected-(U5-IO4-Pad10)") (class "Default")
      (node (ref "U5") (pin "10") (pinfunction "IO4_10") (pintype "bidirectional"))
    )
    (net (code "57") (name "unconnected-(U5-IO5-Pad14)") (class "Default")
      (node (ref "U5") (pin "14") (pinfunction "IO5_14") (pintype "bidirectional"))
    )
    (net (code "58") (name "unconnected-(U5-IO12-Pad4)") (class "Default")
      (node (ref "U5") (pin "4") (pinfunction "IO12_4") (pintype "bidirectional"))
    )
    (net (code "59") (name "unconnected-(U5-IO13-Pad5)") (class "Default")
      (node (ref "U5") (pin "5") (pinfunction "IO13_5") (pintype "bidirectional"))
    )
    (net (code "60") (name "unconnected-(U5-IO14-Pad3)") (class "Default")
      (node (ref "U5") (pin "3") (pinfunction "IO14_3") (pintype "bidirectional"))
    )
    (net (code "61") (name "unconnected-(U5-IO16-Pad17)") (class "Default")
      (node (ref "U5") (pin "17") (pinfunction "IO16_17") (pintype "bidirectional"))
    )
    (net (code "62") (name "unconnected-(U5-TOUT-Pad16)") (class "Default")
      (node (ref "U5") (pin "16") (pinfunction "TOUT_16") (pintype "bidirectional"))
    )
    (net (code "63") (name "ΤΑΒ") (class "Default")
      (node (ref "U2") (pin "TAB") (pinfunction "OUT1_TAB") (pintype "passive"))
    )
  )
)
